# port-expanders.net
KiCad netlist of a schematic drawn in Altium Designer
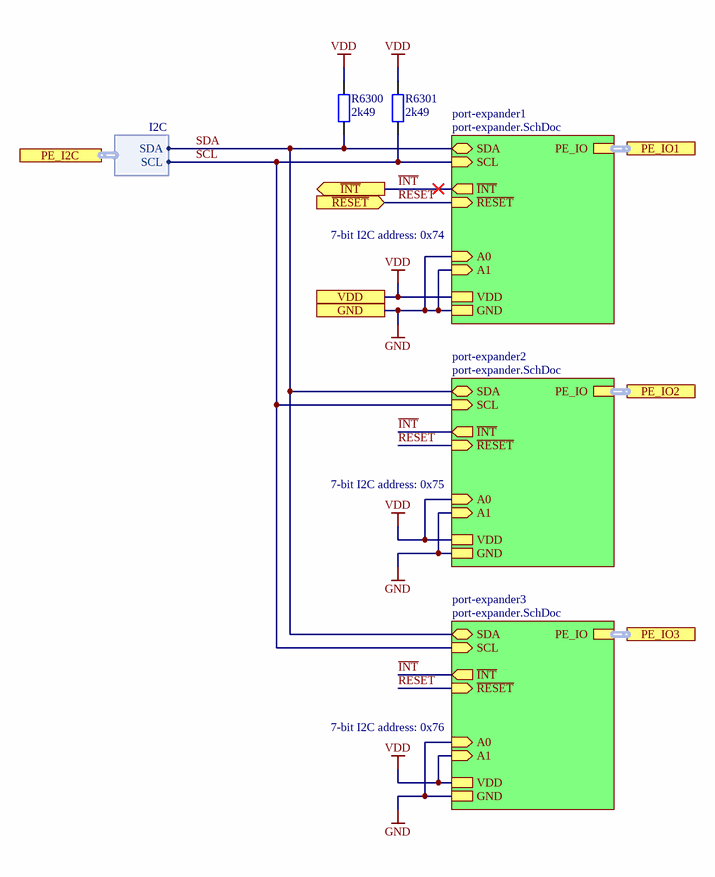
[diagram p0: port-expanders.SchDoc]

(export (version "E")
  (design (tool "Eeschema 10.0.6"))
  (components
    (comp (ref "R6300")
      (value "2k49")
      (footprint "RESC1005X04N")
      (description "SMD Resistor 2k49 0402")
      (fields (field (name "PART NUMBER") "gen_R_2k49_0402") (field (name "TOLERANCE") "1%"))
      (libsource (lib "OE750") (part "R"))
    )
    (comp (ref "R6301")
      (value "2k49")
      (footprint "RESC1005X04N")
      (description "SMD Resistor 2k49 0402")
      (fields (field (name "PART NUMBER") "gen_R_2k49_0402") (field (name "TOLERANCE") "1%"))
      (libsource (lib "OE750") (part "R"))
    )
  )
  (nets
    (net (code "10") (name "/SCL") (class "Default")
      (node (ref "R6301") (pin "1") (pinfunction "1_1") (pintype "passive"))
    )
    (net (code "11") (name "/SDA") (class "Default")
      (node (ref "R6300") (pin "1") (pinfunction "1_1") (pintype "passive"))
    )
    (net (code "14") (name "VDD") (class "Default")
      (node (ref "R6300") (pin "2") (pinfunction "2_2") (pintype "passive"))
      (node (ref "R6301") (pin "2") (pinfunction "2_2") (pintype "passive"))
    )
  )
)
